# MCU_compnts.net
KiCad netlist of a schematic drawn in Altium Designer
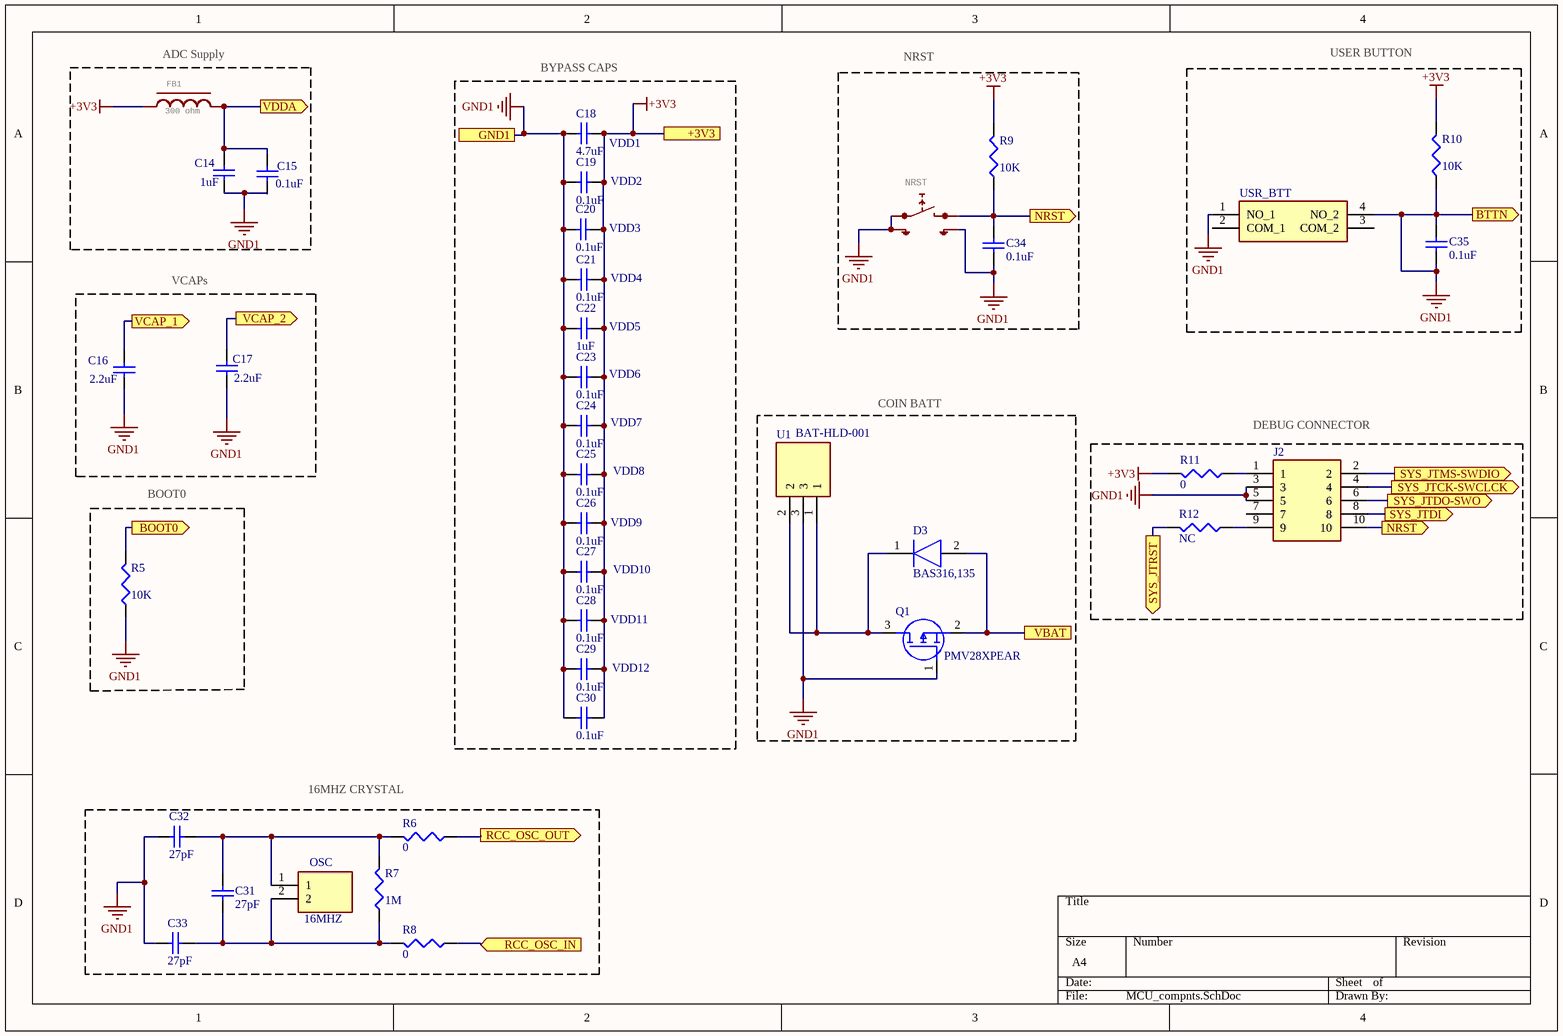
[diagram p0: MCU_compnts.SchDoc]

(export (version "E")
  (design (tool "Eeschema 10.0.6"))
  (components
    (comp (ref "C14")
      (value "1uF")
      (footprint "1608[0603]")
      (description "Capacitor (Semiconductor SIM Model)")
      (fields (field (name "Comment") "Cap Semi") (field (name "PUBLISHER") "Altium Limited"))
      (libsource (lib "Miscellaneous Devices") (part "Cap Semi"))
    )
    (comp (ref "C15")
      (value "0.1uF")
      (footprint "1608[0603]")
      (description "Capacitor (Semiconductor SIM Model)")
      (fields (field (name "Comment") "Cap Semi") (field (name "PUBLISHER") "Altium Limited"))
      (libsource (lib "Miscellaneous Devices") (part "Cap Semi"))
    )
    (comp (ref "C16")
      (value "2.2uF")
      (footprint "1608[0603]")
      (description "Capacitor (Semiconductor SIM Model)")
      (fields (field (name "Comment") "Cap Semi") (field (name "PUBLISHER") "Altium Limited"))
      (libsource (lib "Miscellaneous Devices") (part "Cap Semi"))
    )
    (comp (ref "C17")
      (value "2.2uF")
      (footprint "1608[0603]")
      (description "Capacitor (Semiconductor SIM Model)")
      (fields (field (name "Comment") "Cap Semi") (field (name "PUBLISHER") "Altium Limited"))
      (libsource (lib "Miscellaneous Devices") (part "Cap Semi"))
    )
    (comp (ref "C18")
      (value "4.7uF")
      (footprint "1608[0603]")
      (description "Capacitor (Semiconductor SIM Model)")
      (fields (field (name "Comment") "Cap Semi") (field (name "PUBLISHER") "Altium Limited"))
      (libsource (lib "Miscellaneous Devices") (part "Cap Semi"))
    )
    (comp (ref "C19")
      (value "0.1uF")
      (footprint "1608[0603]")
      (description "Capacitor (Semiconductor SIM Model)")
      (fields (field (name "Comment") "Cap Semi") (field (name "PUBLISHER") "Altium Limited"))
      (libsource (lib "Miscellaneous Devices") (part "Cap Semi"))
    )
    (comp (ref "C20")
      (value "0.1uF")
      (footprint "1608[0603]")
      (description "Capacitor (Semiconductor SIM Model)")
      (fields (field (name "Comment") "Cap Semi") (field (name "PUBLISHER") "Altium Limited"))
      (libsource (lib "Miscellaneous Devices") (part "Cap Semi"))
    )
    (comp (ref "C21")
      (value "0.1uF")
      (footprint "1608[0603]")
      (description "Capacitor (Semiconductor SIM Model)")
      (fields (field (name "Comment") "Cap Semi") (field (name "PUBLISHER") "Altium Limited"))
      (libsource (lib "Miscellaneous Devices") (part "Cap Semi"))
    )
    (comp (ref "C22")
      (value "1uF")
      (footprint "1608[0603]")
      (description "Capacitor (Semiconductor SIM Model)")
      (fields (field (name "Comment") "Cap Semi") (field (name "PUBLISHER") "Altium Limited"))
      (libsource (lib "Miscellaneous Devices") (part "Cap Semi"))
    )
    (comp (ref "C23")
      (value "0.1uF")
      (footprint "1608[0603]")
      (description "Capacitor (Semiconductor SIM Model)")
      (fields (field (name "Comment") "Cap Semi") (field (name "PUBLISHER") "Altium Limited"))
      (libsource (lib "Miscellaneous Devices") (part "Cap Semi"))
    )
    (comp (ref "C24")
      (value "0.1uF")
      (footprint "1608[0603]")
      (description "Capacitor (Semiconductor SIM Model)")
      (fields (field (name "Comment") "Cap Semi") (field (name "PUBLISHER") "Altium Limited"))
      (libsource (lib "Miscellaneous Devices") (part "Cap Semi"))
    )
    (comp (ref "C25")
      (value "0.1uF")
      (footprint "1608[0603]")
      (description "Capacitor (Semiconductor SIM Model)")
      (fields (field (name "Comment") "Cap Semi") (field (name "PUBLISHER") "Altium Limited"))
      (libsource (lib "Miscellaneous Devices") (part "Cap Semi"))
    )
    (comp (ref "C26")
      (value "0.1uF")
      (footprint "1608[0603]")
      (description "Capacitor (Semiconductor SIM Model)")
      (fields (field (name "Comment") "Cap Semi") (field (name "PUBLISHER") "Altium Limited"))
      (libsource (lib "Miscellaneous Devices") (part "Cap Semi"))
    )
    (comp (ref "C27")
      (value "0.1uF")
      (footprint "1608[0603]")
      (description "Capacitor (Semiconductor SIM Model)")
      (fields (field (name "Comment") "Cap Semi") (field (name "PUBLISHER") "Altium Limited"))
      (libsource (lib "Miscellaneous Devices") (part "Cap Semi"))
    )
    (comp (ref "C28")
      (value "0.1uF")
      (footprint "1608[0603]")
      (description "Capacitor (Semiconductor SIM Model)")
      (fields (field (name "Comment") "Cap Semi") (field (name "PUBLISHER") "Altium Limited"))
      (libsource (lib "Miscellaneous Devices") (part "Cap Semi"))
    )
    (comp (ref "C29")
      (value "0.1uF")
      (footprint "1608[0603]")
      (description "Capacitor (Semiconductor SIM Model)")
      (fields (field (name "Comment") "Cap Semi") (field (name "PUBLISHER") "Altium Limited"))
      (libsource (lib "Miscellaneous Devices") (part "Cap Semi"))
    )
    (comp (ref "C30")
      (value "0.1uF")
      (footprint "1608[0603]")
      (description "Capacitor (Semiconductor SIM Model)")
      (fields (field (name "Comment") "Cap Semi") (field (name "PUBLISHER") "Altium Limited"))
      (libsource (lib "Miscellaneous Devices") (part "Cap Semi"))
    )
    (comp (ref "C31")
      (value "27pF")
      (footprint "1608[0603]")
      (description "Capacitor (Semiconductor SIM Model)")
      (fields (field (name "Comment") "Cap Semi") (field (name "PUBLISHER") "Altium Limited"))
      (libsource (lib "Miscellaneous Devices") (part "Cap Semi"))
    )
    (comp (ref "C32")
      (value "27pF")
      (footprint "1608[0603]")
      (description "Capacitor (Semiconductor SIM Model)")
      (fields (field (name "Comment") "Cap Semi") (field (name "PUBLISHER") "Altium Limited"))
      (libsource (lib "Miscellaneous Devices") (part "Cap Semi"))
    )
    (comp (ref "C33")
      (value "27pF")
      (footprint "1608[0603]")
      (description "Capacitor (Semiconductor SIM Model)")
      (fields (field (name "Comment") "Cap Semi") (field (name "PUBLISHER") "Altium Limited"))
      (libsource (lib "Miscellaneous Devices") (part "Cap Semi"))
    )
    (comp (ref "C34")
      (value "0.1uF")
      (footprint "1608[0603]")
      (description "Capacitor (Semiconductor SIM Model)")
      (fields (field (name "Comment") "Cap Semi") (field (name "PUBLISHER") "Altium Limited"))
      (libsource (lib "Miscellaneous Devices") (part "Cap Semi"))
    )
    (comp (ref "C35")
      (value "0.1uF")
      (footprint "1608[0603]")
      (description "Capacitor (Semiconductor SIM Model)")
      (fields (field (name "Comment") "Cap Semi") (field (name "PUBLISHER") "Altium Limited"))
      (libsource (lib "Miscellaneous Devices") (part "Cap Semi"))
    )
    (comp (ref "D3")
      (value "BAS316,135")
      (footprint "SamacSys:SOD2512X110N")
      (description "Diode")
      (fields (field (name "MOUSER PART NUMBER") "771-BAS316135"))
      (libsource (lib "SamacSys") (part "BAS316,135"))
    )
    (comp (ref "FB1")
      (value "300 ohm")
      (footprint "0603_INCH")
      (fields (field (name "LIBRARYNAME") "COMPAQ"))
      (libsource (lib "COMPAC (1)") (part "FERRITE-BEAD0603"))
    )
    (comp (ref "J2")
      (value "FTSH-105-01-L-DV-K-P-TR")
      (footprint "SamacSys:FTSH-105-XX-YYY-DV-K-P-TR")
      (description "Connector")
      (fields (field (name "MOUSER PART NUMBER") "200-FTSH10501LDVKPTR"))
      (libsource (lib "SamacSys") (part "FTSH-105-01-L-DV-K-P-TR"))
    )
    (comp (ref "NRST")
      (value "Tactile Switches 6.1x3.7x2.5mm 100gf")
      (footprint "BOTON_LED_SKQYACE010")
      (fields (field (name "LIBRARYNAME") "COMPAQ"))
      (libsource (lib "COMPAC (1)") (part "SKQYACE010"))
    )
    (comp (ref "OSC")
      (value "16MHZ")
      (footprint "SamacSys:ABM3AIG16000MHZ81RT")
      (description "Crystal or Oscillator")
      (fields
        (field (name "MANUFACTURER_PART_NUMBER") "ABM3AIG-16.000MHZ-8-1R-T")
        (field (name "MOUSER PART NUMBER") "815-M3AIG-16-8-1RT")
      )
      (libsource (lib "SamacSys") (part "ABM3AIG-16.000MHZ-8-1R-T"))
    )
    (comp (ref "Q1")
      (value "PMV28XPEAR")
      (footprint "SamacSys:SOT95P230X110-3N")
      (description "MOSFET (P-Channel)")
      (fields (field (name "MOUSER PART NUMBER") "771-PMV28XPEAR"))
      (libsource (lib "SamacSys") (part "PMV28XPEAR"))
    )
    (comp (ref "R5")
      (value "10K")
      (footprint "J1-0603")
      (description "Resistor")
      (fields (field (name "Comment") "Res3") (field (name "PUBLISHER") "Altium Limited"))
      (libsource (lib "Miscellaneous Devices") (part "Res3"))
    )
    (comp (ref "R6")
      (value "0")
      (footprint "J1-0603")
      (description "Resistor")
      (fields (field (name "Comment") "Res3") (field (name "PUBLISHER") "Altium Limited"))
      (libsource (lib "Miscellaneous Devices") (part "Res3"))
    )
    (comp (ref "R7")
      (value "1M")
      (footprint "J1-0603")
      (description "Resistor")
      (fields (field (name "Comment") "Res3") (field (name "PUBLISHER") "Altium Limited"))
      (libsource (lib "Miscellaneous Devices") (part "Res3"))
    )
    (comp (ref "R8")
      (value "0")
      (footprint "J1-0603")
      (description "Resistor")
      (fields (field (name "Comment") "Res3") (field (name "PUBLISHER") "Altium Limited"))
      (libsource (lib "Miscellaneous Devices") (part "Res3"))
    )
    (comp (ref "R9")
      (value "10K")
      (footprint "J1-0603")
      (description "Resistor")
      (fields (field (name "Comment") "Res3") (field (name "PUBLISHER") "Altium Limited"))
      (libsource (lib "Miscellaneous Devices") (part "Res3"))
    )
    (comp (ref "R10")
      (value "10K")
      (footprint "J1-0603")
      (description "Resistor")
      (fields (field (name "Comment") "Res3") (field (name "PUBLISHER") "Altium Limited"))
      (libsource (lib "Miscellaneous Devices") (part "Res3"))
    )
    (comp (ref "R11")
      (value "0")
      (footprint "J1-0603")
      (description "Resistor")
      (fields (field (name "Comment") "Res3") (field (name "PUBLISHER") "Altium Limited"))
      (libsource (lib "Miscellaneous Devices") (part "Res3"))
    )
    (comp (ref "R12")
      (value "NC")
      (footprint "J1-0603")
      (description "Resistor")
      (fields (field (name "Comment") "Res3") (field (name "PUBLISHER") "Altium Limited"))
      (libsource (lib "Miscellaneous Devices") (part "Res3"))
    )
    (comp (ref "U1")
      (value "BAT-HLD-001")
      (footprint "SamacSys:BATHLD001")
      (description "Undefined or Miscellaneous")
      (fields (field (name "MOUSER PART NUMBER") "712-BAT-HLD-001"))
      (libsource (lib "SamacSys") (part "BAT-HLD-001"))
    )
    (comp (ref "USR_BTT")
      (value "KSC621GLFS")
      (footprint "SamacSys:KSC621GLFS")
      (description "Switch")
      (fields (field (name "MOUSER PART NUMBER") "611-KSC621GLFS"))
      (libsource (lib "SamacSys") (part "KSC621GLFS"))
    )
  )
  (nets
    (net (code "1") (name "+3V3") (class "Default")
      (node (ref "C18") (pin "1") (pinfunction "1_1") (pintype "passive"))
      (node (ref "C19") (pin "1") (pinfunction "1_1") (pintype "passive"))
      (node (ref "C20") (pin "1") (pinfunction "1_1") (pintype "passive"))
      (node (ref "C21") (pin "1") (pinfunction "1_1") (pintype "passive"))
      (node (ref "C22") (pin "1") (pinfunction "1_1") (pintype "passive"))
      (node (ref "C23") (pin "1") (pinfunction "1_1") (pintype "passive"))
      (node (ref "C24") (pin "1") (pinfunction "1_1") (pintype "passive"))
      (node (ref "C25") (pin "1") (pinfunction "1_1") (pintype "passive"))
      (node (ref "C26") (pin "1") (pinfunction "1_1") (pintype "passive"))
      (node (ref "C27") (pin "1") (pinfunction "1_1") (pintype "passive"))
      (node (ref "C28") (pin "1") (pinfunction "1_1") (pintype "passive"))
      (node (ref "C29") (pin "1") (pinfunction "1_1") (pintype "passive"))
      (node (ref "C30") (pin "1") (pinfunction "1_1") (pintype "passive"))
      (node (ref "FB1") (pin "1") (pinfunction "1_1") (pintype "passive"))
      (node (ref "R10") (pin "2") (pinfunction "2_2") (pintype "passive"))
      (node (ref "R11") (pin "2") (pinfunction "2_2") (pintype "passive"))
      (node (ref "R9") (pin "2") (pinfunction "2_2") (pintype "passive"))
    )
    (net (code "2") (name "/BOOT0") (class "Default")
      (node (ref "R5") (pin "2") (pinfunction "2_2") (pintype "passive"))
    )
    (net (code "3") (name "/NRST") (class "Default")
      (node (ref "C34") (pin "1") (pinfunction "1_1") (pintype "passive"))
      (node (ref "J2") (pin "10") (pinfunction "10_10") (pintype "passive"))
      (node (ref "NRST") (pin "2") (pinfunction "2.1_2") (pintype "passive"))
      (node (ref "R9") (pin "1") (pinfunction "1_1") (pintype "passive"))
    )
    (net (code "4") (name "/RCC_OSC_IN") (class "Default")
      (node (ref "R8") (pin "1") (pinfunction "1_1") (pintype "passive"))
    )
    (net (code "5") (name "/RCC_OSC_OUT") (class "Default")
      (node (ref "R6") (pin "1") (pinfunction "1_1") (pintype "passive"))
    )
    (net (code "6") (name "/SYS_JTCK-SWCLCK") (class "Default")
      (node (ref "J2") (pin "4") (pinfunction "4_4") (pintype "passive"))
    )
    (net (code "7") (name "/SYS_JTDI") (class "Default")
      (node (ref "J2") (pin "8") (pinfunction "8_8") (pintype "passive"))
    )
    (net (code "8") (name "/SYS_JTDO-SWO") (class "Default")
      (node (ref "J2") (pin "6") (pinfunction "6_6") (pintype "passive"))
    )
    (net (code "9") (name "/SYS_JTMS-SWDIO") (class "Default")
      (node (ref "J2") (pin "2") (pinfunction "2_2") (pintype "passive"))
    )
    (net (code "10") (name "/SYS_JTRST") (class "Default")
      (node (ref "R12") (pin "2") (pinfunction "2_2") (pintype "passive"))
    )
    (net (code "11") (name "/VBAT") (class "Default")
      (node (ref "D3") (pin "2") (pinfunction "A_2") (pintype "passive"))
      (node (ref "Q1") (pin "2") (pinfunction "S_2") (pintype "passive"))
    )
    (net (code "12") (name "/VCAP_1") (class "Default")
      (node (ref "C16") (pin "2") (pinfunction "2_2") (pintype "passive"))
    )
    (net (code "13") (name "/VCAP_2") (class "Default")
      (node (ref "C17") (pin "2") (pinfunction "2_2") (pintype "passive"))
    )
    (net (code "14") (name "/VDDA") (class "Default")
      (node (ref "C14") (pin "2") (pinfunction "2_2") (pintype "passive"))
      (node (ref "C15") (pin "2") (pinfunction "2_2") (pintype "passive"))
      (node (ref "FB1") (pin "2") (pinfunction "2_2") (pintype "passive"))
    )
    (net (code "15") (name "GND1") (class "Default")
      (node (ref "C14") (pin "1") (pinfunction "1_1") (pintype "passive"))
      (node (ref "C15") (pin "1") (pinfunction "1_1") (pintype "passive"))
      (node (ref "C16") (pin "1") (pinfunction "1_1") (pintype "passive"))
      (node (ref "C17") (pin "1") (pinfunction "1_1") (pintype "passive"))
      (node (ref "C18") (pin "2") (pinfunction "2_2") (pintype "passive"))
      (node (ref "C19") (pin "2") (pinfunction "2_2") (pintype "passive"))
      (node (ref "C20") (pin "2") (pinfunction "2_2") (pintype "passive"))
      (node (ref "C21") (pin "2") (pinfunction "2_2") (pintype "passive"))
      (node (ref "C22") (pin "2") (pinfunction "2_2") (pintype "passive"))
      (node (ref "C23") (pin "2") (pinfunction "2_2") (pintype "passive"))
      (node (ref "C24") (pin "2") (pinfunction "2_2") (pintype "passive"))
      (node (ref "C25") (pin "2") (pinfunction "2_2") (pintype "passive"))
      (node (ref "C26") (pin "2") (pinfunction "2_2") (pintype "passive"))
      (node (ref "C27") (pin "2") (pinfunction "2_2") (pintype "passive"))
      (node (ref "C28") (pin "2") (pinfunction "2_2") (pintype "passive"))
      (node (ref "C29") (pin "2") (pinfunction "2_2") (pintype "passive"))
      (node (ref "C30") (pin "2") (pinfunction "2_2") (pintype "passive"))
      (node (ref "C32") (pin "1") (pinfunction "1_1") (pintype "passive"))
      (node (ref "C33") (pin "2") (pinfunction "2_2") (pintype "passive"))
      (node (ref "C34") (pin "2") (pinfunction "2_2") (pintype "passive"))
      (node (ref "C35") (pin "1") (pinfunction "1_1") (pintype "passive"))
      (node (ref "C35") (pin "2") (pinfunction "2_2") (pintype "passive"))
      (node (ref "J2") (pin "3") (pinfunction "3_3") (pintype "passive"))
      (node (ref "J2") (pin "5") (pinfunction "5_5") (pintype "passive"))
      (node (ref "NRST") (pin "1") (pinfunction "1.1_1") (pintype "passive"))
      (node (ref "NRST") (pin "GND1") (pinfunction "SH_GND1") (pintype "passive"))
      (node (ref "NRST") (pin "GND2") (pinfunction "SH1_GND2") (pintype "passive"))
      (node (ref "Q1") (pin "1") (pinfunction "G_1") (pintype "passive"))
      (node (ref "R10") (pin "1") (pinfunction "1_1") (pintype "passive"))
      (node (ref "R5") (pin "1") (pinfunction "1_1") (pintype "passive"))
      (node (ref "U1") (pin "3") (pinfunction "3_3") (pintype "passive"))
      (node (ref "USR_BTT") (pin "1") (pinfunction "NO_1_1") (pintype "passive"))
      (node (ref "USR_BTT") (pin "4") (pinfunction "NO_2_4") (pintype "passive"))
    )
    (net (code "16") (name "Net-(C31-Pad1)") (class "Default")
      (node (ref "C31") (pin "1") (pinfunction "1_1") (pintype "passive"))
      (node (ref "C32") (pin "2") (pinfunction "2_2") (pintype "passive"))
      (node (ref "OSC") (pin "1") (pinfunction "1_1") (pintype "passive"))
      (node (ref "R6") (pin "2") (pinfunction "2_2") (pintype "passive"))
      (node (ref "R7") (pin "2") (pinfunction "2_2") (pintype "passive"))
    )
    (net (code "17") (name "Net-(C31-Pad2)") (class "Default")
      (node (ref "C31") (pin "2") (pinfunction "2_2") (pintype "passive"))
      (node (ref "C33") (pin "1") (pinfunction "1_1") (pintype "passive"))
      (node (ref "OSC") (pin "2") (pinfunction "2_2") (pintype "passive"))
      (node (ref "R7") (pin "1") (pinfunction "1_1") (pintype "passive"))
      (node (ref "R8") (pin "2") (pinfunction "2_2") (pintype "passive"))
    )
    (net (code "18") (name "Net-(D3-K)") (class "Default")
      (node (ref "D3") (pin "1") (pinfunction "K_1") (pintype "passive"))
      (node (ref "Q1") (pin "3") (pinfunction "D_3") (pintype "passive"))
      (node (ref "U1") (pin "1") (pinfunction "1_1") (pintype "passive"))
      (node (ref "U1") (pin "2") (pinfunction "2_2") (pintype "passive"))
    )
    (net (code "19") (name "Net-(J2-Pad1)") (class "Default")
      (node (ref "J2") (pin "1") (pinfunction "1_1") (pintype "passive"))
      (node (ref "R11") (pin "1") (pinfunction "1_1") (pintype "passive"))
    )
    (net (code "20") (name "Net-(J2-Pad9)") (class "Default")
      (node (ref "J2") (pin "9") (pinfunction "9_9") (pintype "passive"))
      (node (ref "R12") (pin "1") (pinfunction "1_1") (pintype "passive"))
    )
    (net (code "21") (name "unconnected-(J2-Pad7)") (class "Default")
      (node (ref "J2") (pin "7") (pinfunction "7_7") (pintype "passive"))
    )
    (net (code "22") (name "unconnected-(USR_BTT-COM_1-Pad2)") (class "Default")
      (node (ref "USR_BTT") (pin "2") (pinfunction "COM_1_2") (pintype "passive"))
    )
    (net (code "23") (name "unconnected-(USR_BTT-COM_2-Pad3)") (class "Default")
      (node (ref "USR_BTT") (pin "3") (pinfunction "COM_2_3") (pintype "passive"))
    )
  )
)
